# Remote_Control_Sheet.net
KiCad netlist of a schematic drawn in Altium Designer
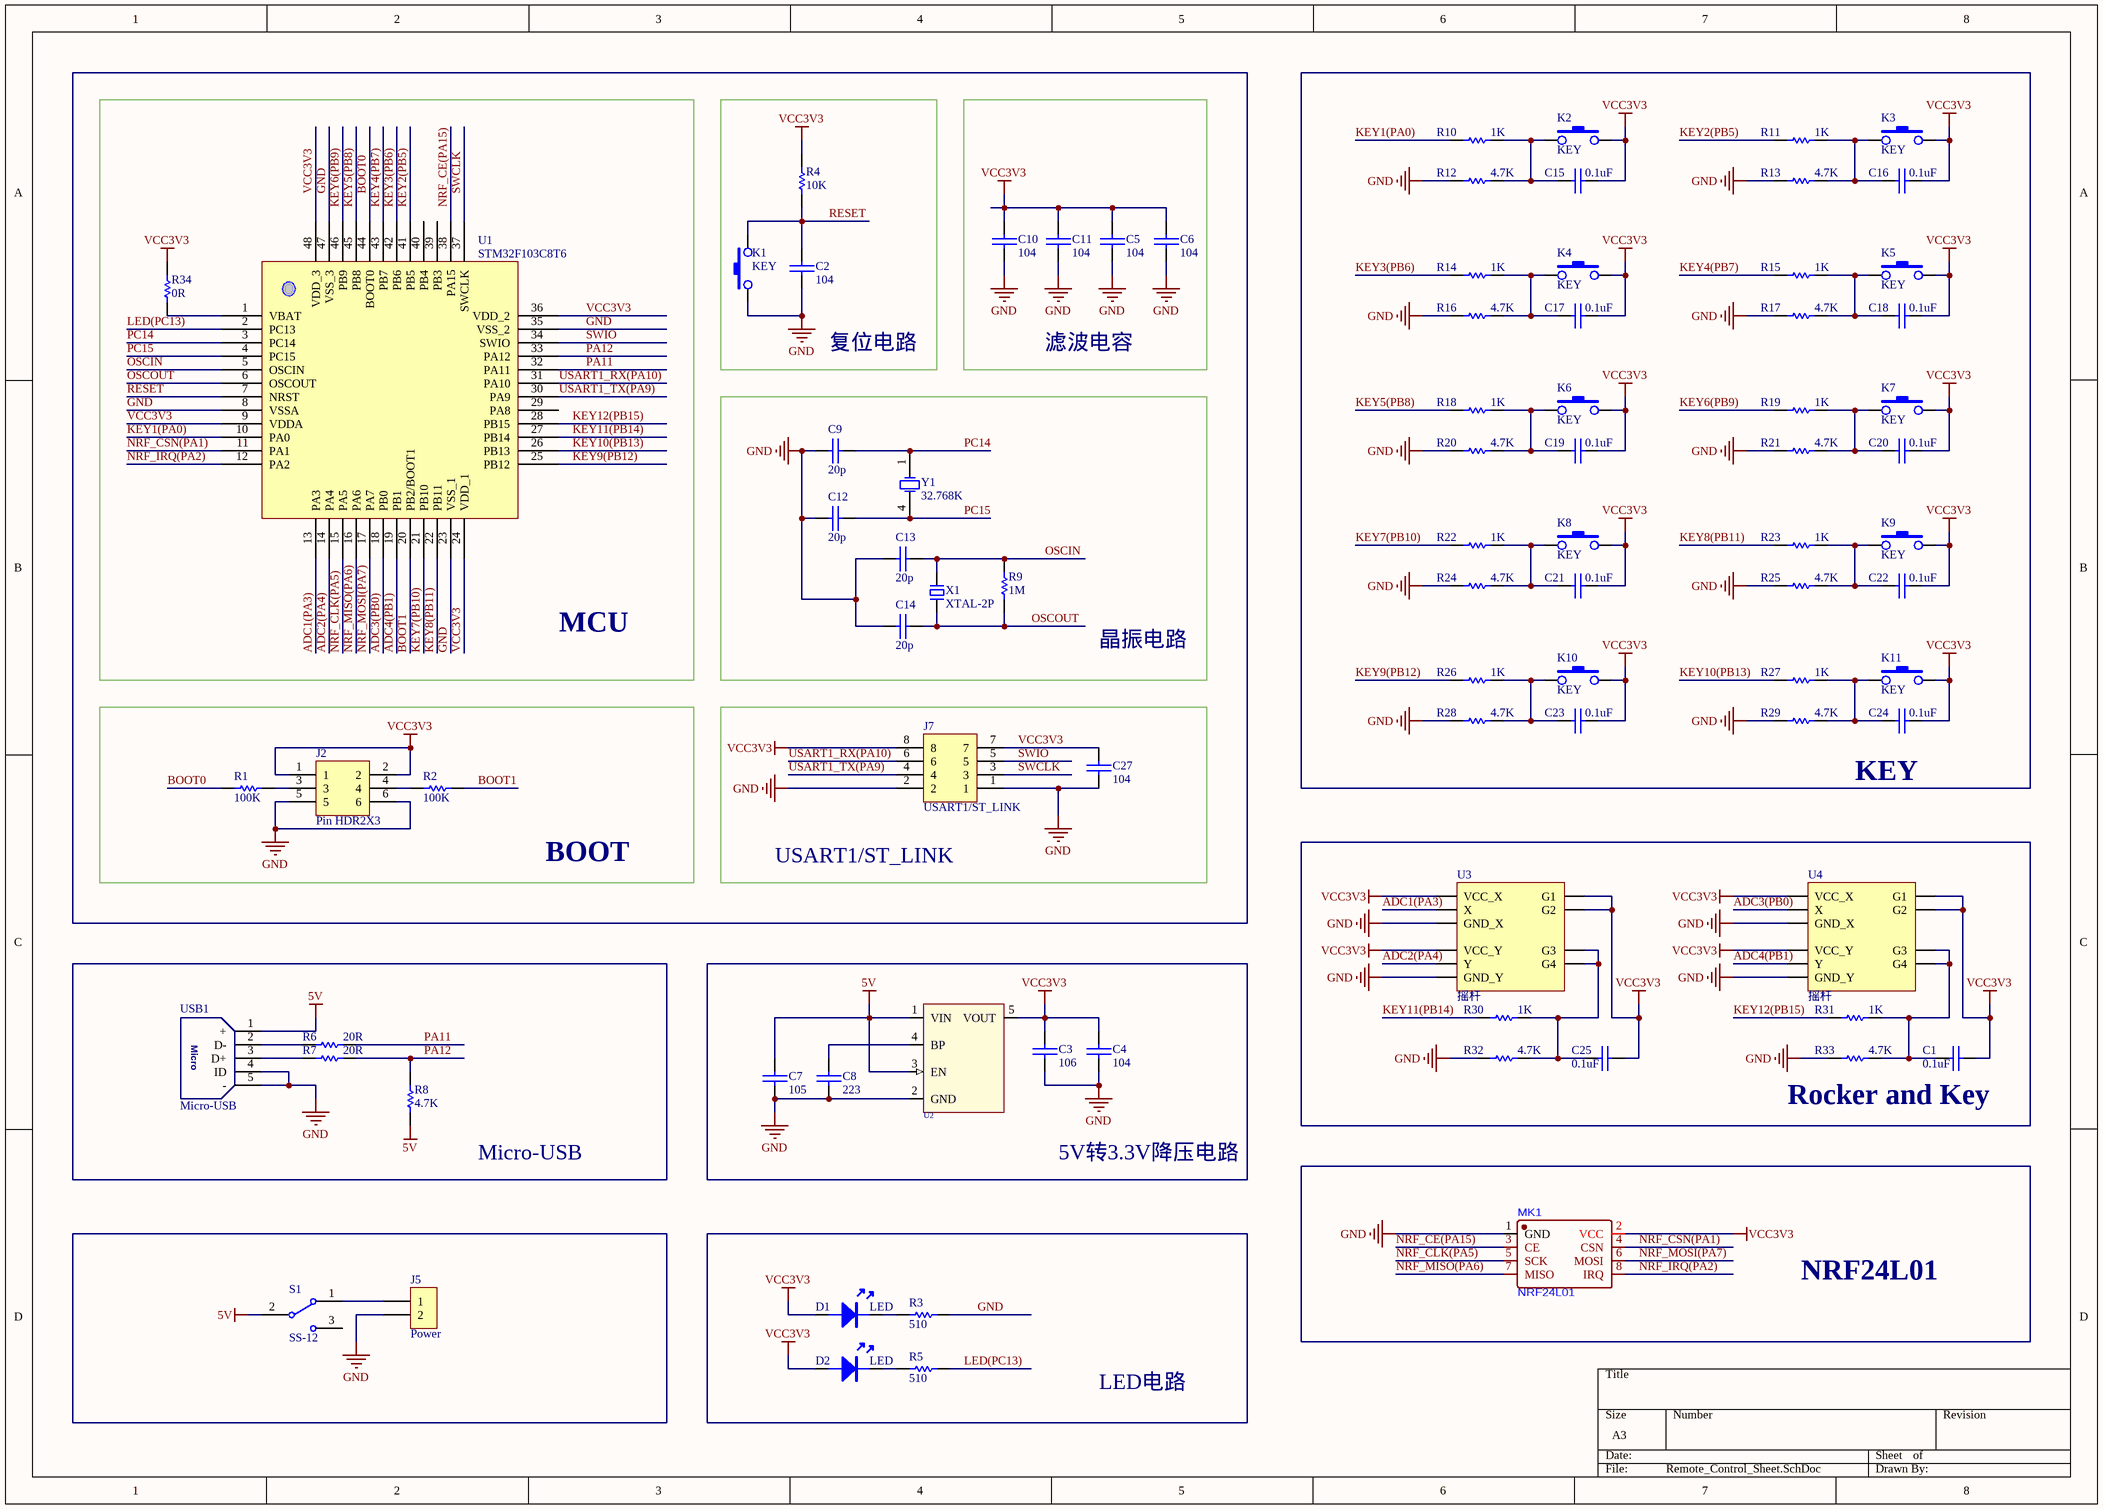
[diagram p0: Remote_Control_Sheet.SchDoc]

(export (version "E")
  (design (tool "Eeschema 10.0.6"))
  (components
    (comp (ref "C1")
      (value "0.1uF")
      (footprint "0603C")
      (description "无极性电容")
      (libsource (lib "电容") (part "CAP"))
    )
    (comp (ref "C2")
      (value "104")
      (footprint "0603C")
      (description "无极性电容")
      (libsource (lib "电容") (part "CAP"))
    )
    (comp (ref "C3")
      (value "106")
      (footprint "0603C")
      (description "无极性电容")
      (libsource (lib "电容") (part "CAP"))
    )
    (comp (ref "C4")
      (value "104")
      (footprint "0603C")
      (description "无极性电容")
      (libsource (lib "电容") (part "CAP"))
    )
    (comp (ref "C5")
      (value "104")
      (footprint "0603C")
      (description "无极性电容")
      (libsource (lib "电容") (part "CAP"))
    )
    (comp (ref "C6")
      (value "104")
      (footprint "0603C")
      (description "无极性电容")
      (libsource (lib "电容") (part "CAP"))
    )
    (comp (ref "C7")
      (value "105")
      (footprint "0603C")
      (description "无极性电容")
      (libsource (lib "电容") (part "CAP"))
    )
    (comp (ref "C8")
      (value "223")
      (footprint "0603C")
      (description "无极性电容")
      (libsource (lib "电容") (part "CAP"))
    )
    (comp (ref "C9")
      (value "20p")
      (footprint "0603C")
      (description "无极性电容")
      (libsource (lib "电容") (part "CAP"))
    )
    (comp (ref "C10")
      (value "104")
      (footprint "0603C")
      (description "无极性电容")
      (libsource (lib "电容") (part "CAP"))
    )
    (comp (ref "C11")
      (value "104")
      (footprint "0603C")
      (description "无极性电容")
      (libsource (lib "电容") (part "CAP"))
    )
    (comp (ref "C12")
      (value "20p")
      (footprint "0603C")
      (description "无极性电容")
      (libsource (lib "电容") (part "CAP"))
    )
    (comp (ref "C13")
      (value "20p")
      (footprint "0603C")
      (description "无极性电容")
      (libsource (lib "电容") (part "CAP"))
    )
    (comp (ref "C14")
      (value "20p")
      (footprint "0603C")
      (description "无极性电容")
      (libsource (lib "电容") (part "CAP"))
    )
    (comp (ref "C15")
      (value "0.1uF")
      (footprint "0603C")
      (description "无极性电容")
      (libsource (lib "电容") (part "CAP"))
    )
    (comp (ref "C16")
      (value "0.1uF")
      (footprint "0603C")
      (description "无极性电容")
      (libsource (lib "电容") (part "CAP"))
    )
    (comp (ref "C17")
      (value "0.1uF")
      (footprint "0603C")
      (description "无极性电容")
      (libsource (lib "电容") (part "CAP"))
    )
    (comp (ref "C18")
      (value "0.1uF")
      (footprint "0603C")
      (description "无极性电容")
      (libsource (lib "电容") (part "CAP"))
    )
    (comp (ref "C19")
      (value "0.1uF")
      (footprint "0603C")
      (description "无极性电容")
      (libsource (lib "电容") (part "CAP"))
    )
    (comp (ref "C20")
      (value "0.1uF")
      (footprint "0603C")
      (description "无极性电容")
      (libsource (lib "电容") (part "CAP"))
    )
    (comp (ref "C21")
      (value "0.1uF")
      (footprint "0603C")
      (description "无极性电容")
      (libsource (lib "电容") (part "CAP"))
    )
    (comp (ref "C22")
      (value "0.1uF")
      (footprint "0603C")
      (description "无极性电容")
      (libsource (lib "电容") (part "CAP"))
    )
    (comp (ref "C23")
      (value "0.1uF")
      (footprint "0603C")
      (description "无极性电容")
      (libsource (lib "电容") (part "CAP"))
    )
    (comp (ref "C24")
      (value "0.1uF")
      (footprint "0603C")
      (description "无极性电容")
      (libsource (lib "电容") (part "CAP"))
    )
    (comp (ref "C25")
      (value "0.1uF")
      (footprint "0603C")
      (description "无极性电容")
      (libsource (lib "电容") (part "CAP"))
    )
    (comp (ref "C27")
      (value "104")
      (footprint "0603C")
      (description "无极性电容")
      (libsource (lib "电容") (part "CAP"))
    )
    (comp (ref "D1") (value "LED") (footprint "LED-0603B") (libsource (lib "LED") (part "LED")))
    (comp (ref "D2") (value "LED") (footprint "LED-0603B") (libsource (lib "LED") (part "LED")))
    (comp (ref "J2")
      (value "Pin HDR2X3")
      (footprint "Pin HDR2X3/2.54mm-S")
      (libsource (lib "排针") (part "Pin HDR2X3"))
    )
    (comp (ref "J5")
      (value "Power")
      (footprint "Pin HDR1X2/2.54mm-S")
      (libsource (lib "排针") (part "Pin HDR1X2"))
    )
    (comp (ref "J7")
      (value "USART1/ST_LINK")
      (footprint "Pin HDR2X4/2.54mm-S")
      (libsource (lib "排针") (part "Pin HDR2X4"))
    )
    (comp (ref "K1") (value "KEY") (footprint "SMD-3X6X5") (libsource (lib "轻触开关") (part "KEY")))
    (comp (ref "K2") (value "KEY") (footprint "SMD-3X6X2.5") (libsource (lib "轻触开关") (part "KEY")))
    (comp (ref "K3") (value "KEY") (footprint "SMD-3X6X2.5") (libsource (lib "轻触开关") (part "KEY")))
    (comp (ref "K4") (value "KEY") (footprint "SMD-3X6X2.5") (libsource (lib "轻触开关") (part "KEY")))
    (comp (ref "K5") (value "KEY") (footprint "SMD-3X6X2.5") (libsource (lib "轻触开关") (part "KEY")))
    (comp (ref "K6") (value "KEY") (footprint "SMD-3X6X2.5") (libsource (lib "轻触开关") (part "KEY")))
    (comp (ref "K7") (value "KEY") (footprint "SMD-3X6X2.5") (libsource (lib "轻触开关") (part "KEY")))
    (comp (ref "K8") (value "KEY") (footprint "SMD-3X6X2.5") (libsource (lib "轻触开关") (part "KEY")))
    (comp (ref "K9") (value "KEY") (footprint "SMD-3X6X2.5") (libsource (lib "轻触开关") (part "KEY")))
    (comp (ref "K10") (value "KEY") (footprint "SMD-3X6X2.5") (libsource (lib "轻触开关") (part "KEY")))
    (comp (ref "K11") (value "KEY") (footprint "SMD-3X6X2.5") (libsource (lib "轻触开关") (part "KEY")))
    (comp (ref "MK1")
      (value "NRF24L01")
      (footprint "WIRELM-SMD_NRF24L01")
      (libsource (lib "zy lib") (part "NRF24L01"))
    )
    (comp (ref "R1") (value "100K") (footprint "0603R") (libsource (lib "电阻") (part "RES")))
    (comp (ref "R2") (value "100K") (footprint "0603R") (libsource (lib "电阻") (part "RES")))
    (comp (ref "R3") (value "510") (footprint "0603R") (libsource (lib "电阻") (part "RES")))
    (comp (ref "R4") (value "10K") (footprint "0603R") (libsource (lib "电阻") (part "RES")))
    (comp (ref "R5") (value "510") (footprint "0603R") (libsource (lib "电阻") (part "RES")))
    (comp (ref "R6") (value "20R") (footprint "0603R") (libsource (lib "电阻") (part "RES")))
    (comp (ref "R7") (value "20R") (footprint "0603R") (libsource (lib "电阻") (part "RES")))
    (comp (ref "R8") (value "4.7K") (footprint "0603R") (libsource (lib "电阻") (part "RES")))
    (comp (ref "R9") (value "1M") (footprint "0603R") (libsource (lib "电阻") (part "RES")))
    (comp (ref "R10") (value "1K") (footprint "0603R") (libsource (lib "电阻") (part "RES")))
    (comp (ref "R11") (value "1K") (footprint "0603R") (libsource (lib "电阻") (part "RES")))
    (comp (ref "R12") (value "4.7K") (footprint "0603R") (libsource (lib "电阻") (part "RES")))
    (comp (ref "R13") (value "4.7K") (footprint "0603R") (libsource (lib "电阻") (part "RES")))
    (comp (ref "R14") (value "1K") (footprint "0603R") (libsource (lib "电阻") (part "RES")))
    (comp (ref "R15") (value "1K") (footprint "0603R") (libsource (lib "电阻") (part "RES")))
    (comp (ref "R16") (value "4.7K") (footprint "0603R") (libsource (lib "电阻") (part "RES")))
    (comp (ref "R17") (value "4.7K") (footprint "0603R") (libsource (lib "电阻") (part "RES")))
    (comp (ref "R18") (value "1K") (footprint "0603R") (libsource (lib "电阻") (part "RES")))
    (comp (ref "R19") (value "1K") (footprint "0603R") (libsource (lib "电阻") (part "RES")))
    (comp (ref "R20") (value "4.7K") (footprint "0603R") (libsource (lib "电阻") (part "RES")))
    (comp (ref "R21") (value "4.7K") (footprint "0603R") (libsource (lib "电阻") (part "RES")))
    (comp (ref "R22") (value "1K") (footprint "0603R") (libsource (lib "电阻") (part "RES")))
    (comp (ref "R23") (value "1K") (footprint "0603R") (libsource (lib "电阻") (part "RES")))
    (comp (ref "R24") (value "4.7K") (footprint "0603R") (libsource (lib "电阻") (part "RES")))
    (comp (ref "R25") (value "4.7K") (footprint "0603R") (libsource (lib "电阻") (part "RES")))
    (comp (ref "R26") (value "1K") (footprint "0603R") (libsource (lib "电阻") (part "RES")))
    (comp (ref "R27") (value "1K") (footprint "0603R") (libsource (lib "电阻") (part "RES")))
    (comp (ref "R28") (value "4.7K") (footprint "0603R") (libsource (lib "电阻") (part "RES")))
    (comp (ref "R29") (value "4.7K") (footprint "0603R") (libsource (lib "电阻") (part "RES")))
    (comp (ref "R30") (value "1K") (footprint "0603R") (libsource (lib "电阻") (part "RES")))
    (comp (ref "R31") (value "1K") (footprint "0603R") (libsource (lib "电阻") (part "RES")))
    (comp (ref "R32") (value "4.7K") (footprint "0603R") (libsource (lib "电阻") (part "RES")))
    (comp (ref "R33") (value "4.7K") (footprint "0603R") (libsource (lib "电阻") (part "RES")))
    (comp (ref "R34") (value "0R") (footprint "0603R") (libsource (lib "电阻") (part "RES")))
    (comp (ref "S1") (value "SS-12") (footprint "SK-12D07VG3") (libsource (lib "电源开关") (part "SS-12X")))
    (comp (ref "U1")
      (value "STM32F103C8T6")
      (footprint "48P")
      (libsource (lib "STM32F103C8T6") (part "STM32F103C8T6"))
    )
    (comp (ref "U2")
      (value "RT9193")
      (fields (field (name "ICA_PARTNUM") "$$2191094$$RT9193-15CU5") (field (name "PART NUMBER") "TMP-13"))
      (libsource (lib "STM32F103C8T6") (part "RT9193X_5P"))
    )
    (comp (ref "U3") (value "摇杆") (footprint "摇杆_直插_圆半径13_10电气脚_4固定脚") (libsource (lib "zy lib") (part "摇杆")))
    (comp (ref "U4") (value "摇杆") (footprint "摇杆_直插_圆半径13_10电气脚_4固定脚") (libsource (lib "zy lib") (part "摇杆")))
    (comp (ref "USB1")
      (value "Micro-USB")
      (footprint "USB-MICRO_A")
      (libsource (lib "USB") (part "Micro-USB"))
    )
    (comp (ref "X1")
      (value "XTAL-2P")
      (footprint "OSC HC-49S")
      (description "2脚无源脚晶振")
      (libsource (lib "晶振") (part "XTAL-2P"))
    )
    (comp (ref "Y1")
      (value "32.768K")
      (footprint "MC-306")
      (description "Crystal Oscillator")
      (fields (field (name "PUBLISHER") "Altium Limited"))
      (libsource (lib "STM32F103C8T6") (part "XTAL"))
    )
  )
  (nets
    (net (code "1") (name "/ADC1(PA3)") (class "Default")
      (node (ref "U1") (pin "13") (pinfunction "PA3_13") (pintype "passive"))
      (node (ref "U3") (pin "6") (pinfunction "X_6") (pintype "passive"))
    )
    (net (code "2") (name "/ADC2(PA4)") (class "Default")
      (node (ref "U1") (pin "14") (pinfunction "PA4_14") (pintype "passive"))
      (node (ref "U3") (pin "9") (pinfunction "Y_9") (pintype "passive"))
    )
    (net (code "3") (name "/ADC3(PB0)") (class "Default")
      (node (ref "U1") (pin "18") (pinfunction "PB0_18") (pintype "passive"))
      (node (ref "U4") (pin "6") (pinfunction "X_6") (pintype "passive"))
    )
    (net (code "4") (name "/ADC4(PB1)") (class "Default")
      (node (ref "U1") (pin "19") (pinfunction "PB1_19") (pintype "passive"))
      (node (ref "U4") (pin "9") (pinfunction "Y_9") (pintype "passive"))
    )
    (net (code "5") (name "/BOOT0") (class "Default")
      (node (ref "R1") (pin "2") (pinfunction "2_2") (pintype "passive"))
      (node (ref "U1") (pin "44") (pinfunction "BOOT0_44") (pintype "passive"))
    )
    (net (code "6") (name "/BOOT1") (class "Default")
      (node (ref "R2") (pin "1") (pinfunction "1_1") (pintype "passive"))
      (node (ref "U1") (pin "20") (pinfunction "PB2/BOOT1_20") (pintype "passive"))
    )
    (net (code "7") (name "/KEY1(PA0)") (class "Default")
      (node (ref "R10") (pin "1") (pinfunction "1_1") (pintype "passive"))
      (node (ref "U1") (pin "10") (pinfunction "PA0_10") (pintype "passive"))
    )
    (net (code "8") (name "/KEY2(PB5)") (class "Default")
      (node (ref "R11") (pin "1") (pinfunction "1_1") (pintype "passive"))
      (node (ref "U1") (pin "41") (pinfunction "PB5_41") (pintype "passive"))
    )
    (net (code "9") (name "/KEY3(PB6)") (class "Default")
      (node (ref "R14") (pin "1") (pinfunction "1_1") (pintype "passive"))
      (node (ref "U1") (pin "42") (pinfunction "PB6_42") (pintype "passive"))
    )
    (net (code "10") (name "/KEY4(PB7)") (class "Default")
      (node (ref "R15") (pin "1") (pinfunction "1_1") (pintype "passive"))
      (node (ref "U1") (pin "43") (pinfunction "PB7_43") (pintype "passive"))
    )
    (net (code "11") (name "/KEY5(PB8)") (class "Default")
      (node (ref "R18") (pin "1") (pinfunction "1_1") (pintype "passive"))
      (node (ref "U1") (pin "45") (pinfunction "PB8_45") (pintype "passive"))
    )
    (net (code "12") (name "/KEY6(PB9)") (class "Default")
      (node (ref "R19") (pin "1") (pinfunction "1_1") (pintype "passive"))
      (node (ref "U1") (pin "46") (pinfunction "PB9_46") (pintype "passive"))
    )
    (net (code "13") (name "/KEY7(PB10)") (class "Default")
      (node (ref "R22") (pin "1") (pinfunction "1_1") (pintype "passive"))
      (node (ref "U1") (pin "21") (pinfunction "PB10_21") (pintype "passive"))
    )
    (net (code "14") (name "/KEY8(PB11)") (class "Default")
      (node (ref "R23") (pin "1") (pinfunction "1_1") (pintype "passive"))
      (node (ref "U1") (pin "22") (pinfunction "PB11_22") (pintype "passive"))
    )
    (net (code "15") (name "/KEY9(PB12)") (class "Default")
      (node (ref "R26") (pin "1") (pinfunction "1_1") (pintype "passive"))
      (node (ref "U1") (pin "25") (pinfunction "PB12_25") (pintype "passive"))
    )
    (net (code "16") (name "/KEY10(PB13)") (class "Default")
      (node (ref "R27") (pin "1") (pinfunction "1_1") (pintype "passive"))
      (node (ref "U1") (pin "26") (pinfunction "PB13_26") (pintype "passive"))
    )
    (net (code "17") (name "/KEY11(PB14)") (class "Default")
      (node (ref "R30") (pin "1") (pinfunction "1_1") (pintype "passive"))
      (node (ref "U1") (pin "27") (pinfunction "PB14_27") (pintype "passive"))
    )
    (net (code "18") (name "/KEY12(PB15)") (class "Default")
      (node (ref "R31") (pin "1") (pinfunction "1_1") (pintype "passive"))
      (node (ref "U1") (pin "28") (pinfunction "PB15_28") (pintype "passive"))
    )
    (net (code "19") (name "/LED(PC13)") (class "Default")
      (node (ref "R5") (pin "1") (pinfunction "1_1") (pintype "passive"))
      (node (ref "U1") (pin "2") (pinfunction "PC13_2") (pintype "passive"))
    )
    (net (code "20") (name "/NRF_CE(PA15)") (class "Default")
      (node (ref "MK1") (pin "3") (pinfunction "CE_3") (pintype "passive"))
      (node (ref "U1") (pin "38") (pinfunction "PA15_38") (pintype "passive"))
    )
    (net (code "21") (name "/NRF_CLK(PA5)") (class "Default")
      (node (ref "MK1") (pin "5") (pinfunction "SCK_5") (pintype "passive"))
      (node (ref "U1") (pin "15") (pinfunction "PA5_15") (pintype "passive"))
    )
    (net (code "22") (name "/NRF_CSN(PA1)") (class "Default")
      (node (ref "MK1") (pin "4") (pinfunction "CSN_4") (pintype "passive"))
      (node (ref "U1") (pin "11") (pinfunction "PA1_11") (pintype "passive"))
    )
    (net (code "23") (name "/NRF_IRQ(PA2)") (class "Default")
      (node (ref "MK1") (pin "8") (pinfunction "IRQ_8") (pintype "passive"))
      (node (ref "U1") (pin "12") (pinfunction "PA2_12") (pintype "passive"))
    )
    (net (code "24") (name "/NRF_MISO(PA6)") (class "Default")
      (node (ref "MK1") (pin "7") (pinfunction "MISO_7") (pintype "passive"))
      (node (ref "U1") (pin "16") (pinfunction "PA6_16") (pintype "passive"))
    )
    (net (code "25") (name "/NRF_MOSI(PA7)") (class "Default")
      (node (ref "MK1") (pin "6") (pinfunction "MOSI_6") (pintype "passive"))
      (node (ref "U1") (pin "17") (pinfunction "PA7_17") (pintype "passive"))
    )
    (net (code "26") (name "/OSCIN") (class "Default")
      (node (ref "C13") (pin "2") (pinfunction "2_2") (pintype "passive"))
      (node (ref "R9") (pin "1") (pinfunction "1_1") (pintype "passive"))
      (node (ref "U1") (pin "5") (pinfunction "OSCIN_5") (pintype "passive"))
      (node (ref "X1") (pin "2") (pinfunction "2_2") (pintype "passive"))
    )
    (net (code "27") (name "/OSCOUT") (class "Default")
      (node (ref "C14") (pin "2") (pinfunction "2_2") (pintype "passive"))
      (node (ref "R9") (pin "2") (pinfunction "2_2") (pintype "passive"))
      (node (ref "U1") (pin "6") (pinfunction "OSCOUT_6") (pintype "passive"))
      (node (ref "X1") (pin "1") (pinfunction "1_1") (pintype "passive"))
    )
    (net (code "28") (name "/PA11") (class "Default")
      (node (ref "R6") (pin "1") (pinfunction "1_1") (pintype "passive"))
      (node (ref "U1") (pin "32") (pinfunction "PA11_32") (pintype "passive"))
    )
    (net (code "29") (name "/PA12") (class "Default")
      (node (ref "R7") (pin "1") (pinfunction "1_1") (pintype "passive"))
      (node (ref "R8") (pin "1") (pinfunction "1_1") (pintype "passive"))
      (node (ref "U1") (pin "33") (pinfunction "PA12_33") (pintype "passive"))
    )
    (net (code "30") (name "/PC14") (class "Default")
      (node (ref "C9") (pin "2") (pinfunction "2_2") (pintype "passive"))
      (node (ref "U1") (pin "3") (pinfunction "PC14_3") (pintype "passive"))
      (node (ref "Y1") (pin "1") (pinfunction "OSC1_1") (pintype "passive"))
    )
    (net (code "31") (name "/PC15") (class "Default")
      (node (ref "C12") (pin "2") (pinfunction "2_2") (pintype "passive"))
      (node (ref "U1") (pin "4") (pinfunction "PC15_4") (pintype "passive"))
      (node (ref "Y1") (pin "4") (pinfunction "OSC2_4") (pintype "passive"))
    )
    (net (code "32") (name "/RESET") (class "Default")
      (node (ref "C2") (pin "2") (pinfunction "2_2") (pintype "passive"))
      (node (ref "K1") (pin "3") (pinfunction "3_3") (pintype "passive"))
      (node (ref "R4") (pin "1") (pinfunction "1_1") (pintype "passive"))
      (node (ref "U1") (pin "7") (pinfunction "NRST_7") (pintype "passive"))
    )
    (net (code "33") (name "/SWCLK") (class "Default")
      (node (ref "J7") (pin "3") (pinfunction "3_3") (pintype "passive"))
      (node (ref "U1") (pin "37") (pinfunction "SWCLK_37") (pintype "passive"))
    )
    (net (code "34") (name "/SWIO") (class "Default")
      (node (ref "J7") (pin "5") (pinfunction "5_5") (pintype "passive"))
      (node (ref "U1") (pin "34") (pinfunction "SWIO_34") (pintype "passive"))
    )
    (net (code "35") (name "/USART1_RX(PA10)") (class "Default")
      (node (ref "J7") (pin "6") (pinfunction "6_6") (pintype "passive"))
      (node (ref "U1") (pin "31") (pinfunction "PA10_31") (pintype "passive"))
    )
    (net (code "36") (name "/USART1_TX(PA9)") (class "Default")
      (node (ref "J7") (pin "4") (pinfunction "4_4") (pintype "passive"))
      (node (ref "U1") (pin "30") (pinfunction "PA9_30") (pintype "passive"))
    )
    (net (code "37") (name "5V") (class "Default")
      (node (ref "C7") (pin "2") (pinfunction "2_2") (pintype "passive"))
      (node (ref "R8") (pin "2") (pinfunction "2_2") (pintype "passive"))
      (node (ref "S1") (pin "2") (pinfunction "2_2") (pintype "passive"))
      (node (ref "U2") (pin "1") (pinfunction "VIN_1") (pintype "power_in"))
      (node (ref "U2") (pin "3") (pinfunction "EN_3") (pintype "input"))
      (node (ref "USB1") (pin "1") (pinfunction "+_1") (pintype "passive"))
    )
    (net (code "38") (name "GND") (class "Default")
      (node (ref "C10") (pin "1") (pinfunction "1_1") (pintype "passive"))
      (node (ref "C11") (pin "1") (pinfunction "1_1") (pintype "passive"))
      (node (ref "C12") (pin "1") (pinfunction "1_1") (pintype "passive"))
      (node (ref "C13") (pin "1") (pinfunction "1_1") (pintype "passive"))
      (node (ref "C14") (pin "1") (pinfunction "1_1") (pintype "passive"))
      (node (ref "C2") (pin "1") (pinfunction "1_1") (pintype "passive"))
      (node (ref "C27") (pin "1") (pinfunction "1_1") (pintype "passive"))
      (node (ref "C3") (pin "1") (pinfunction "1_1") (pintype "passive"))
      (node (ref "C4") (pin "1") (pinfunction "1_1") (pintype "passive"))
      (node (ref "C5") (pin "1") (pinfunction "1_1") (pintype "passive"))
      (node (ref "C6") (pin "1") (pinfunction "1_1") (pintype "passive"))
      (node (ref "C7") (pin "1") (pinfunction "1_1") (pintype "passive"))
      (node (ref "C8") (pin "1") (pinfunction "1_1") (pintype "passive"))
      (node (ref "C9") (pin "1") (pinfunction "1_1") (pintype "passive"))
      (node (ref "J2") (pin "5") (pinfunction "5_5") (pintype "passive"))
      (node (ref "J2") (pin "6") (pinfunction "6_6") (pintype "passive"))
      (node (ref "J5") (pin "2") (pinfunction "2_2") (pintype "passive"))
      (node (ref "J7") (pin "1") (pinfunction "1_1") (pintype "passive"))
      (node (ref "J7") (pin "2") (pinfunction "2_2") (pintype "passive"))
      (node (ref "K1") (pin "1") (pinfunction "1_1") (pintype "passive"))
      (node (ref "MK1") (pin "1") (pinfunction "GND_1") (pintype "passive"))
      (node (ref "R12") (pin "1") (pinfunction "1_1") (pintype "passive"))
      (node (ref "R13") (pin "1") (pinfunction "1_1") (pintype "passive"))
      (node (ref "R16") (pin "1") (pinfunction "1_1") (pintype "passive"))
      (node (ref "R17") (pin "1") (pinfunction "1_1") (pintype "passive"))
      (node (ref "R20") (pin "1") (pinfunction "1_1") (pintype "passive"))
      (node (ref "R21") (pin "1") (pinfunction "1_1") (pintype "passive"))
      (node (ref "R24") (pin "1") (pinfunction "1_1") (pintype "passive"))
      (node (ref "R25") (pin "1") (pinfunction "1_1") (pintype "passive"))
      (node (ref "R28") (pin "1") (pinfunction "1_1") (pintype "passive"))
      (node (ref "R29") (pin "1") (pinfunction "1_1") (pintype "passive"))
      (node (ref "R3") (pin "1") (pinfunction "1_1") (pintype "passive"))
      (node (ref "R32") (pin "1") (pinfunction "1_1") (pintype "passive"))
      (node (ref "R33") (pin "1") (pinfunction "1_1") (pintype "passive"))
      (node (ref "U1") (pin "23") (pinfunction "VSS_1_23") (pintype "passive"))
      (node (ref "U1") (pin "35") (pinfunction "VSS_2_35") (pintype "passive"))
      (node (ref "U1") (pin "47") (pinfunction "VSS_3_47") (pintype "passive"))
      (node (ref "U1") (pin "8") (pinfunction "VSSA_8") (pintype "passive"))
      (node (ref "U2") (pin "2") (pinfunction "GND_2") (pintype "power_in"))
      (node (ref "U3") (pin "10") (pinfunction "GND_Y_10") (pintype "passive"))
      (node (ref "U3") (pin "7") (pinfunction "GND_X_7") (pintype "passive"))
      (node (ref "U4") (pin "10") (pinfunction "GND_Y_10") (pintype "passive"))
      (node (ref "U4") (pin "7") (pinfunction "GND_X_7") (pintype "passive"))
      (node (ref "USB1") (pin "4") (pinfunction "ID_4") (pintype "passive"))
      (node (ref "USB1") (pin "5") (pinfunction "-_5") (pintype "passive"))
    )
    (net (code "39") (name "Net-(C15-Pad1)") (class "Default")
      (node (ref "C15") (pin "1") (pinfunction "1_1") (pintype "passive"))
      (node (ref "K2") (pin "1") (pinfunction "1_1") (pintype "passive"))
      (node (ref "R10") (pin "2") (pinfunction "2_2") (pintype "passive"))
      (node (ref "R12") (pin "2") (pinfunction "2_2") (pintype "passive"))
    )
    (net (code "40") (name "Net-(C16-Pad1)") (class "Default")
      (node (ref "C16") (pin "1") (pinfunction "1_1") (pintype "passive"))
      (node (ref "K3") (pin "1") (pinfunction "1_1") (pintype "passive"))
      (node (ref "R11") (pin "2") (pinfunction "2_2") (pintype "passive"))
      (node (ref "R13") (pin "2") (pinfunction "2_2") (pintype "passive"))
    )
    (net (code "41") (name "Net-(C17-Pad1)") (class "Default")
      (node (ref "C17") (pin "1") (pinfunction "1_1") (pintype "passive"))
      (node (ref "K4") (pin "1") (pinfunction "1_1") (pintype "passive"))
      (node (ref "R14") (pin "2") (pinfunction "2_2") (pintype "passive"))
      (node (ref "R16") (pin "2") (pinfunction "2_2") (pintype "passive"))
    )
    (net (code "42") (name "Net-(C18-Pad1)") (class "Default")
      (node (ref "C18") (pin "1") (pinfunction "1_1") (pintype "passive"))
      (node (ref "K5") (pin "1") (pinfunction "1_1") (pintype "passive"))
      (node (ref "R15") (pin "2") (pinfunction "2_2") (pintype "passive"))
      (node (ref "R17") (pin "2") (pinfunction "2_2") (pintype "passive"))
    )
    (net (code "43") (name "Net-(C19-Pad1)") (class "Default")
      (node (ref "C19") (pin "1") (pinfunction "1_1") (pintype "passive"))
      (node (ref "K6") (pin "1") (pinfunction "1_1") (pintype "passive"))
      (node (ref "R18") (pin "2") (pinfunction "2_2") (pintype "passive"))
      (node (ref "R20") (pin "2") (pinfunction "2_2") (pintype "passive"))
    )
    (net (code "44") (name "Net-(C20-Pad1)") (class "Default")
      (node (ref "C20") (pin "1") (pinfunction "1_1") (pintype "passive"))
      (node (ref "K7") (pin "1") (pinfunction "1_1") (pintype "passive"))
      (node (ref "R19") (pin "2") (pinfunction "2_2") (pintype "passive"))
      (node (ref "R21") (pin "2") (pinfunction "2_2") (pintype "passive"))
    )
    (net (code "45") (name "Net-(C21-Pad1)") (class "Default")
      (node (ref "C21") (pin "1") (pinfunction "1_1") (pintype "passive"))
      (node (ref "K8") (pin "1") (pinfunction "1_1") (pintype "passive"))
      (node (ref "R22") (pin "2") (pinfunction "2_2") (pintype "passive"))
      (node (ref "R24") (pin "2") (pinfunction "2_2") (pintype "passive"))
    )
    (net (code "46") (name "Net-(C22-Pad1)") (class "Default")
      (node (ref "C22") (pin "1") (pinfunction "1_1") (pintype "passive"))
      (node (ref "K9") (pin "1") (pinfunction "1_1") (pintype "passive"))
      (node (ref "R23") (pin "2") (pinfunction "2_2") (pintype "passive"))
      (node (ref "R25") (pin "2") (pinfunction "2_2") (pintype "passive"))
    )
    (net (code "47") (name "Net-(C23-Pad1)") (class "Default")
      (node (ref "C23") (pin "1") (pinfunction "1_1") (pintype "passive"))
      (node (ref "K10") (pin "1") (pinfunction "1_1") (pintype "passive"))
      (node (ref "R26") (pin "2") (pinfunction "2_2") (pintype "passive"))
      (node (ref "R28") (pin "2") (pinfunction "2_2") (pintype "passive"))
    )
    (net (code "48") (name "Net-(C24-Pad1)") (class "Default")
      (node (ref "C24") (pin "1") (pinfunction "1_1") (pintype "passive"))
      (node (ref "K11") (pin "1") (pinfunction "1_1") (pintype "passive"))
      (node (ref "R27") (pin "2") (pinfunction "2_2") (pintype "passive"))
      (node (ref "R29") (pin "2") (pinfunction "2_2") (pintype "passive"))
    )
    (net (code "49") (name "Net-(D1-PadK)") (class "Default")
      (node (ref "D1") (pin "K") (pinfunction "K_K") (pintype "passive"))
      (node (ref "R3") (pin "2") (pinfunction "2_2") (pintype "passive"))
    )
    (net (code "50") (name "Net-(D2-PadK)") (class "Default")
      (node (ref "D2") (pin "K") (pinfunction "K_K") (pintype "passive"))
      (node (ref "R5") (pin "2") (pinfunction "2_2") (pintype "passive"))
    )
    (net (code "51") (name "Net-(J2-Pad3)") (class "Default")
      (node (ref "J2") (pin "3") (pinfunction "3_3") (pintype "passive"))
      (node (ref "R1") (pin "1") (pinfunction "1_1") (pintype "passive"))
    )
    (net (code "52") (name "Net-(J2-Pad4)") (class "Default")
      (node (ref "J2") (pin "4") (pinfunction "4_4") (pintype "passive"))
      (node (ref "R2") (pin "2") (pinfunction "2_2") (pintype "passive"))
    )
    (net (code "53") (name "Net-(J5-Pad1)") (class "Default")
      (node (ref "J5") (pin "1") (pinfunction "1_1") (pintype "passive"))
      (node (ref "S1") (pin "1") (pinfunction "1_1") (pintype "passive"))
    )
    (net (code "54") (name "Net-(U1-VBAT)") (class "Default")
      (node (ref "R34") (pin "1") (pinfunction "1_1") (pintype "passive"))
      (node (ref "U1") (pin "1") (pinfunction "VBAT_1") (pintype "passive"))
    )
    (net (code "55") (name "Net-(U2-BP)") (class "Default")
      (node (ref "C8") (pin "2") (pinfunction "2_2") (pintype "passive"))
      (node (ref "U2") (pin "4") (pinfunction "BP_4") (pintype "passive"))
    )
    (net (code "56") (name "Net-(U3-G3)") (class "Default")
      (node (ref "C25") (pin "1") (pinfunction "1_1") (pintype "passive"))
      (node (ref "R30") (pin "2") (pinfunction "2_2") (pintype "passive"))
      (node (ref "R32") (pin "2") (pinfunction "2_2") (pintype "passive"))
      (node (ref "U3") (pin "3") (pinfunction "G3_3") (pintype "passive"))
      (node (ref "U3") (pin "4") (pinfunction "G4_4") (pintype "passive"))
    )
    (net (code "57") (name "Net-(U4-G3)") (class "Default")
      (node (ref "C1") (pin "1") (pinfunction "1_1") (pintype "passive"))
      (node (ref "R31") (pin "2") (pinfunction "2_2") (pintype "passive"))
      (node (ref "R33") (pin "2") (pinfunction "2_2") (pintype "passive"))
      (node (ref "U4") (pin "3") (pinfunction "G3_3") (pintype "passive"))
      (node (ref "U4") (pin "4") (pinfunction "G4_4") (pintype "passive"))
    )
    (net (code "58") (name "Net-(USB1-D+)") (class "Default")
      (node (ref "R7") (pin "2") (pinfunction "2_2") (pintype "passive"))
      (node (ref "USB1") (pin "3") (pinfunction "D+_3") (pintype "passive"))
    )
    (net (code "59") (name "Net-(USB1-D-)") (class "Default")
      (node (ref "R6") (pin "2") (pinfunction "2_2") (pintype "passive"))
      (node (ref "USB1") (pin "2") (pinfunction "D-_2") (pintype "passive"))
    )
    (net (code "60") (name "VCC3V3") (class "Default")
      (node (ref "C1") (pin "2") (pinfunction "2_2") (pintype "passive"))
      (node (ref "C10") (pin "2") (pinfunction "2_2") (pintype "passive"))
      (node (ref "C11") (pin "2") (pinfunction "2_2") (pintype "passive"))
      (node (ref "C15") (pin "2") (pinfunction "2_2") (pintype "passive"))
      (node (ref "C16") (pin "2") (pinfunction "2_2") (pintype "passive"))
      (node (ref "C17") (pin "2") (pinfunction "2_2") (pintype "passive"))
      (node (ref "C18") (pin "2") (pinfunction "2_2") (pintype "passive"))
      (node (ref "C19") (pin "2") (pinfunction "2_2") (pintype "passive"))
      (node (ref "C20") (pin "2") (pinfunction "2_2") (pintype "passive"))
      (node (ref "C21") (pin "2") (pinfunction "2_2") (pintype "passive"))
      (node (ref "C22") (pin "2") (pinfunction "2_2") (pintype "passive"))
      (node (ref "C23") (pin "2") (pinfunction "2_2") (pintype "passive"))
      (node (ref "C24") (pin "2") (pinfunction "2_2") (pintype "passive"))
      (node (ref "C25") (pin "2") (pinfunction "2_2") (pintype "passive"))
      (node (ref "C27") (pin "2") (pinfunction "2_2") (pintype "passive"))
      (node (ref "C3") (pin "2") (pinfunction "2_2") (pintype "passive"))
      (node (ref "C4") (pin "2") (pinfunction "2_2") (pintype "passive"))
      (node (ref "C5") (pin "2") (pinfunction "2_2") (pintype "passive"))
      (node (ref "C6") (pin "2") (pinfunction "2_2") (pintype "passive"))
      (node (ref "D1") (pin "A") (pinfunction "A_A") (pintype "passive"))
      (node (ref "D2") (pin "A") (pinfunction "A_A") (pintype "passive"))
      (node (ref "J2") (pin "1") (pinfunction "1_1") (pintype "passive"))
      (node (ref "J2") (pin "2") (pinfunction "2_2") (pintype "passive"))
      (node (ref "J7") (pin "7") (pinfunction "7_7") (pintype "passive"))
      (node (ref "J7") (pin "8") (pinfunction "8_8") (pintype "passive"))
      (node (ref "K10") (pin "3") (pinfunction "3_3") (pintype "passive"))
      (node (ref "K11") (pin "3") (pinfunction "3_3") (pintype "passive"))
      (node (ref "K2") (pin "3") (pinfunction "3_3") (pintype "passive"))
      (node (ref "K3") (pin "3") (pinfunction "3_3") (pintype "passive"))
      (node (ref "K4") (pin "3") (pinfunction "3_3") (pintype "passive"))
      (node (ref "K5") (pin "3") (pinfunction "3_3") (pintype "passive"))
      (node (ref "K6") (pin "3") (pinfunction "3_3") (pintype "passive"))
      (node (ref "K7") (pin "3") (pinfunction "3_3") (pintype "passive"))
      (node (ref "K8") (pin "3") (pinfunction "3_3") (pintype "passive"))
      (node (ref "K9") (pin "3") (pinfunction "3_3") (pintype "passive"))
      (node (ref "MK1") (pin "2") (pinfunction "VCC_2") (pintype "passive"))
      (node (ref "R34") (pin "2") (pinfunction "2_2") (pintype "passive"))
      (node (ref "R4") (pin "2") (pinfunction "2_2") (pintype "passive"))
      (node (ref "U1") (pin "24") (pinfunction "VDD_1_24") (pintype "passive"))
      (node (ref "U1") (pin "36") (pinfunction "VDD_2_36") (pintype "passive"))
      (node (ref "U1") (pin "48") (pinfunction "VDD_3_48") (pintype "passive"))
      (node (ref "U1") (pin "9") (pinfunction "VDDA_9") (pintype "passive"))
      (node (ref "U2") (pin "5") (pinfunction "VOUT_5") (pintype "power_in"))
      (node (ref "U3") (pin "1") (pinfunction "G1_1") (pintype "passive"))
      (node (ref "U3") (pin "2") (pinfunction "G2_2") (pintype "passive"))
      (node (ref "U3") (pin "5") (pinfunction "VCC_X_5") (pintype "passive"))
      (node (ref "U3") (pin "8") (pinfunction "VCC_Y_8") (pintype "passive"))
      (node (ref "U4") (pin "1") (pinfunction "G1_1") (pintype "passive"))
      (node (ref "U4") (pin "2") (pinfunction "G2_2") (pintype "passive"))
      (node (ref "U4") (pin "5") (pinfunction "VCC_X_5") (pintype "passive"))
      (node (ref "U4") (pin "8") (pinfunction "VCC_Y_8") (pintype "passive"))
    )
    (net (code "61") (name "unconnected-(S1-Pad3)") (class "Default")
      (node (ref "S1") (pin "3") (pinfunction "3_3") (pintype "passive"))
    )
    (net (code "62") (name "unconnected-(U1-PA8-Pad29)") (class "Default")
      (node (ref "U1") (pin "29") (pinfunction "PA8_29") (pintype "passive"))
    )
    (net (code "63") (name "unconnected-(U1-PB3-Pad39)") (class "Default")
      (node (ref "U1") (pin "39") (pinfunction "PB3_39") (pintype "passive"))
    )
    (net (code "64") (name "unconnected-(U1-PB4-Pad40)") (class "Default")
      (node (ref "U1") (pin "40") (pinfunction "PB4_40") (pintype "passive"))
    )
  )
)
